# battery_lcl-discharging.net
KiCad netlist of a schematic drawn in Altium Designer
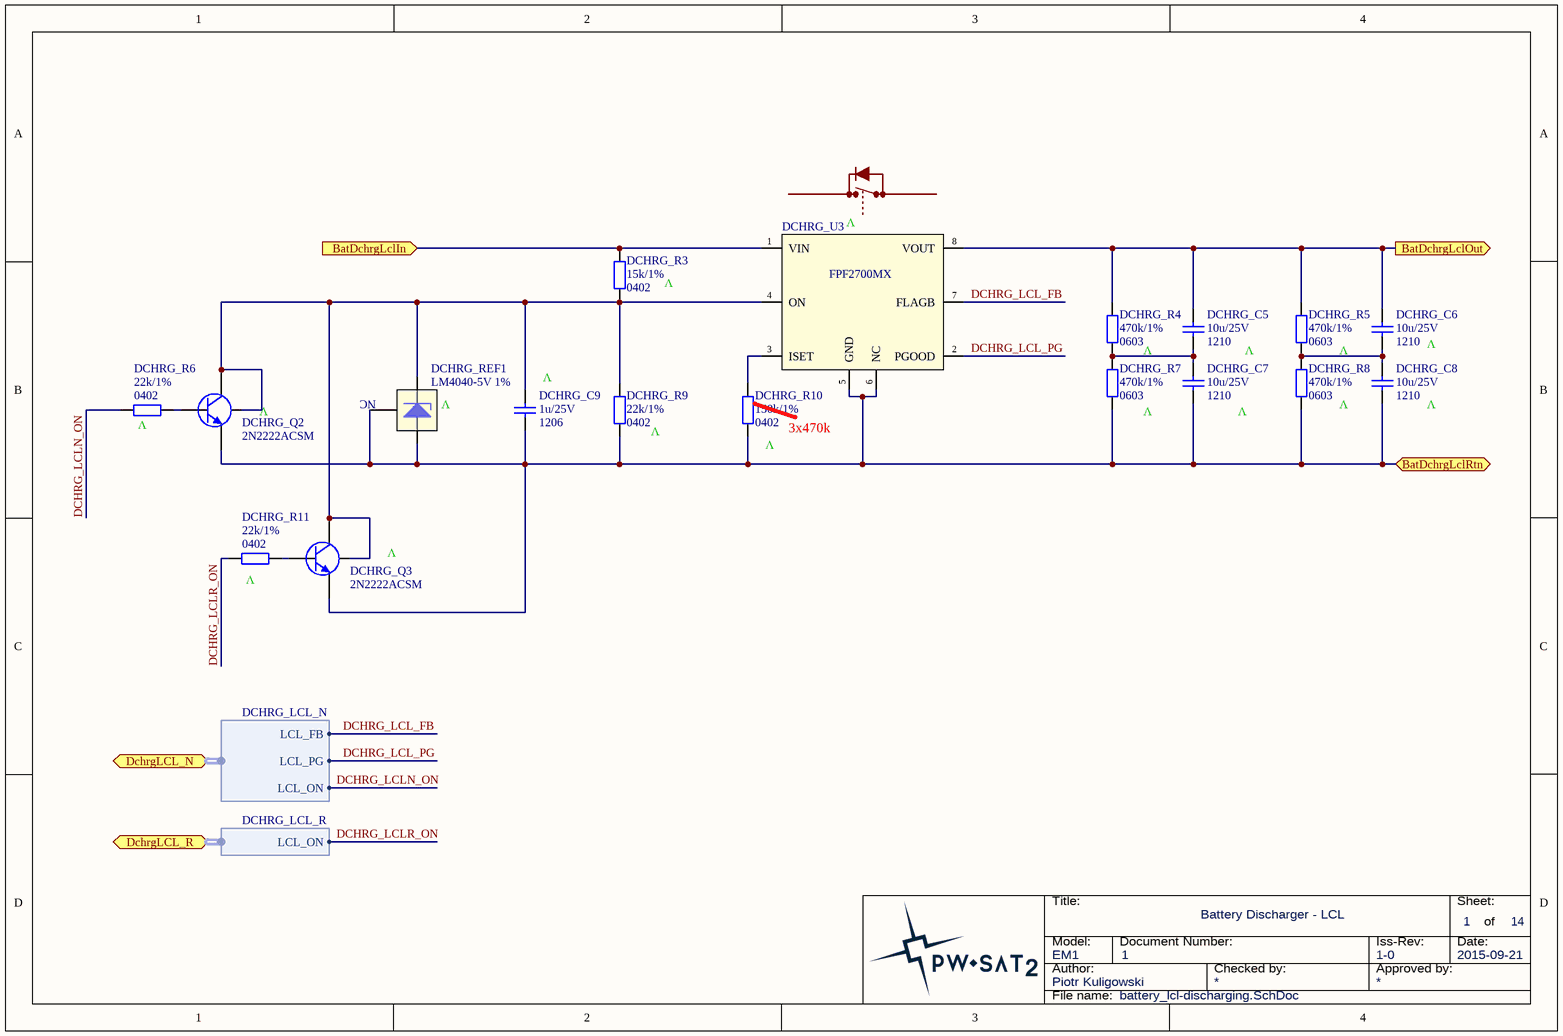
[diagram p0: battery_lcl-discharging.SchDoc]

(export (version "E")
  (design (tool "Eeschema 10.0.6"))
  (components
    (comp (ref "DCHRG_C5")
      (value "10u/25V")
      (footprint "SMD_Capacitor_1210")
      (description "Ceramic Cap Murata Automotive 10u/25V X7R 1210")
      (fields
        (field (name "MANUFACTURER") "Murata")
        (field (name "MANUFACTURERPARTNUMBER") "GCJ32ER71E106KA12L")
        (field (name "PACKAGE") "1210")
      )
      (libsource (lib "capacitors") (part "Cer_GCJ32ER71E106KA12L"))
    )
    (comp (ref "DCHRG_C6")
      (value "10u/25V")
      (footprint "SMD_Capacitor_1210")
      (description "Ceramic Cap Murata Automotive 10u/25V X7R 1210")
      (fields
        (field (name "MANUFACTURER") "Murata")
        (field (name "MANUFACTURERPARTNUMBER") "GCJ32ER71E106KA12L")
        (field (name "PACKAGE") "1210")
      )
      (libsource (lib "capacitors") (part "Cer_GCJ32ER71E106KA12L"))
    )
    (comp (ref "DCHRG_C7")
      (value "10u/25V")
      (footprint "SMD_Capacitor_1210")
      (description "Ceramic Cap Murata Automotive 10u/25V X7R 1210")
      (fields
        (field (name "MANUFACTURER") "Murata")
        (field (name "MANUFACTURERPARTNUMBER") "GCJ32ER71E106KA12L")
        (field (name "PACKAGE") "1210")
      )
      (libsource (lib "capacitors") (part "Cer_GCJ32ER71E106KA12L"))
    )
    (comp (ref "DCHRG_C8")
      (value "10u/25V")
      (footprint "SMD_Capacitor_1210")
      (description "Ceramic Cap Murata Automotive 10u/25V X7R 1210")
      (fields
        (field (name "MANUFACTURER") "Murata")
        (field (name "MANUFACTURERPARTNUMBER") "GCJ32ER71E106KA12L")
        (field (name "PACKAGE") "1210")
      )
      (libsource (lib "capacitors") (part "Cer_GCJ32ER71E106KA12L"))
    )
    (comp (ref "DCHRG_C9")
      (value "1u/25V")
      (footprint "SMD_Capacitor_1206")
      (description "Ceramic Cap Kemet COTS 1u/25V X7R 1206")
      (fields
        (field (name "MANUFACTURERPARTNUMBER") "C1206T105K3RALTU")
        (field (name "MANUFACTURER") "Kemet")
        (field (name "PACKAGE") "1206")
      )
      (libsource (lib "capacitors") (part "Cer_C1206T105K3RALTU"))
    )
    (comp (ref "DCHRG_Q2")
      (value "2N2222ACSM")
      (footprint "LCC1-4_BEC")
      (description "Silicon Planar Epitaxial NPN Transistor.")
      (fields (field (name "MANUFACTURER") "Semelab-TT"))
      (libsource (lib "transistors") (part "2N2222ACSM"))
    )
    (comp (ref "DCHRG_Q3")
      (value "2N2222ACSM")
      (footprint "LCC1-4_BEC")
      (description "Silicon Planar Epitaxial NPN Transistor.")
      (fields (field (name "MANUFACTURER") "Semelab-TT"))
      (libsource (lib "transistors") (part "2N2222ACSM"))
    )
    (comp (ref "DCHRG_R3")
      (value "15k/1%")
      (footprint "SMD_Resistor_0402")
      (description "15k/1% Vishay CRCW 0402 Resistor. 63mW, 100ppm, 50V.")
      (fields
        (field (name "MANUFACTURER") "Vishay")
        (field (name "MANUFACTURERPARTNUMBER") "CRCW040215K0FKxxxx")
        (field (name "PACKAGE") "0402")
      )
      (libsource (lib "resistors") (part "CRCW040215K0FKxxxx"))
    )
    (comp (ref "DCHRG_R4")
      (value "470k/1%")
      (footprint "SMD_Resistor_0603")
      (description "470k/1% Vishay CRCW 0603 Resistor. 100mW, 100ppm, 75V.")
      (fields
        (field (name "MANUFACTURER") "Vishay")
        (field (name "MANUFACTURERPARTNUMBER") "CRCW0603470KFKxxxx")
        (field (name "PACKAGE") "0603")
      )
      (libsource (lib "resistors") (part "CRCW0603470KFKxxxx"))
    )
    (comp (ref "DCHRG_R5")
      (value "470k/1%")
      (footprint "SMD_Resistor_0603")
      (description "470k/1% Vishay CRCW 0603 Resistor. 100mW, 100ppm, 75V.")
      (fields
        (field (name "MANUFACTURER") "Vishay")
        (field (name "MANUFACTURERPARTNUMBER") "CRCW0603470KFKxxxx")
        (field (name "PACKAGE") "0603")
      )
      (libsource (lib "resistors") (part "CRCW0603470KFKxxxx"))
    )
    (comp (ref "DCHRG_R6")
      (value "22k/1%")
      (footprint "SMD_Resistor_0402")
      (description "22k/1% Vishay CRCW 0402 Resistor. 63mW, 100ppm, 50V.")
      (fields
        (field (name "MANUFACTURER") "Vishay")
        (field (name "MANUFACTURERPARTNUMBER") "CRCW040222K0FKxxxx")
        (field (name "PACKAGE") "0402")
      )
      (libsource (lib "resistors") (part "CRCW040222K0FKxxxx"))
    )
    (comp (ref "DCHRG_R7")
      (value "470k/1%")
      (footprint "SMD_Resistor_0603")
      (description "470k/1% Vishay CRCW 0603 Resistor. 100mW, 100ppm, 75V.")
      (fields
        (field (name "MANUFACTURER") "Vishay")
        (field (name "MANUFACTURERPARTNUMBER") "CRCW0603470KFKxxxx")
        (field (name "PACKAGE") "0603")
      )
      (libsource (lib "resistors") (part "CRCW0603470KFKxxxx"))
    )
    (comp (ref "DCHRG_R8")
      (value "470k/1%")
      (footprint "SMD_Resistor_0603")
      (description "470k/1% Vishay CRCW 0603 Resistor. 100mW, 100ppm, 75V.")
      (fields
        (field (name "MANUFACTURER") "Vishay")
        (field (name "MANUFACTURERPARTNUMBER") "CRCW0603470KFKxxxx")
        (field (name "PACKAGE") "0603")
      )
      (libsource (lib "resistors") (part "CRCW0603470KFKxxxx"))
    )
    (comp (ref "DCHRG_R9")
      (value "22k/1%")
      (footprint "SMD_Resistor_0402")
      (description "22k/1% Vishay CRCW 0402 Resistor. 63mW, 100ppm, 50V.")
      (fields
        (field (name "MANUFACTURER") "Vishay")
        (field (name "MANUFACTURERPARTNUMBER") "CRCW040222K0FKxxxx")
        (field (name "PACKAGE") "0402")
      )
      (libsource (lib "") (part "CRCW040222K0FKxxxx_1"))
    )
    (comp (ref "DCHRG_R10")
      (value "150k/1%")
      (footprint "SMD_Resistor_0402")
      (description "150k/1% Vishay CRCW 0402 Resistor. 63mW, 100ppm, 50V.")
      (fields
        (field (name "MANUFACTURER") "Vishay")
        (field (name "MANUFACTURERPARTNUMBER") "CRCW0402150KFKxxxx")
        (field (name "PACKAGE") "0402")
      )
      (libsource (lib "resistors") (part "CRCW0402150KFKxxxx"))
    )
    (comp (ref "DCHRG_R11")
      (value "22k/1%")
      (footprint "SMD_Resistor_0402")
      (description "22k/1% Vishay CRCW 0402 Resistor. 63mW, 100ppm, 50V.")
      (fields
        (field (name "MANUFACTURER") "Vishay")
        (field (name "MANUFACTURERPARTNUMBER") "CRCW040222K0FKxxxx")
        (field (name "PACKAGE") "0402")
      )
      (libsource (lib "resistors") (part "CRCW040222K0FKxxxx"))
    )
    (comp (ref "DCHRG_REF1")
      (value "LM4040-5V 1%")
      (footprint "SOT23-3")
      (description "Shunt V-REF, 5V, 1%, SOT23-3")
      (fields
        (field (name "MANUFACTURER") "Texas Instruments")
        (field (name "MANUFACTURERPARTNUMBER") "LM4040DIM3-5.0")
      )
      (libsource (lib "diodes") (part "LM4040DIM3-5.0"))
    )
    (comp (ref "DCHRG_U3")
      (value "FPF2700MX")
      (footprint "SOIC-8-N")
      (description "Adj over-current protection 0.4-2A, Load Switch")
      (fields (field (name "MANUFACTURER") "Fairchild Semiconductor"))
      (libsource (lib "microcircuits") (part "FPF2700MX"))
    )
  )
  (nets
    (net (code "3") (name "/BatDchrgLclIn") (class "Default")
      (node (ref "DCHRG_R3") (pin "1") (pinfunction "1_1") (pintype "passive"))
      (node (ref "DCHRG_U3") (pin "1") (pinfunction "VIN_1") (pintype "passive"))
    )
    (net (code "4") (name "/BatDchrgLclOut") (class "Default")
      (node (ref "DCHRG_C5") (pin "1") (pinfunction "1_1") (pintype "passive"))
      (node (ref "DCHRG_C6") (pin "1") (pinfunction "1_1") (pintype "passive"))
      (node (ref "DCHRG_R4") (pin "1") (pinfunction "1_1") (pintype "passive"))
      (node (ref "DCHRG_R5") (pin "1") (pinfunction "1_1") (pintype "passive"))
      (node (ref "DCHRG_U3") (pin "8") (pinfunction "VOUT_8") (pintype "passive"))
    )
    (net (code "5") (name "/BatDchrgLclRtn") (class "Default")
      (node (ref "DCHRG_C7") (pin "2") (pinfunction "2_2") (pintype "passive"))
      (node (ref "DCHRG_C8") (pin "2") (pinfunction "2_2") (pintype "passive"))
      (node (ref "DCHRG_C9") (pin "2") (pinfunction "2_2") (pintype "passive"))
      (node (ref "DCHRG_Q2") (pin "E") (pinfunction "E_E") (pintype "passive"))
      (node (ref "DCHRG_Q3") (pin "E") (pinfunction "E_E") (pintype "passive"))
      (node (ref "DCHRG_R10") (pin "2") (pinfunction "2_2") (pintype "passive"))
      (node (ref "DCHRG_R7") (pin "2") (pinfunction "2_2") (pintype "passive"))
      (node (ref "DCHRG_R8") (pin "2") (pinfunction "2_2") (pintype "passive"))
      (node (ref "DCHRG_R9") (pin "2") (pinfunction "2_2") (pintype "passive"))
      (node (ref "DCHRG_REF1") (pin "2") (pinfunction "A_2") (pintype "passive"))
      (node (ref "DCHRG_REF1") (pin "3") (pinfunction "NC_3") (pintype "passive"))
      (node (ref "DCHRG_U3") (pin "5") (pinfunction "GND_5") (pintype "passive"))
      (node (ref "DCHRG_U3") (pin "6") (pinfunction "NC_6") (pintype "passive"))
    )
    (net (code "6") (name "/DCHRG_LCLN_ON") (class "Default")
      (node (ref "DCHRG_R6") (pin "2") (pinfunction "2_2") (pintype "passive"))
    )
    (net (code "7") (name "/DCHRG_LCLR_ON") (class "Default")
      (node (ref "DCHRG_R11") (pin "2") (pinfunction "2_2") (pintype "passive"))
    )
    (net (code "8") (name "/DCHRG_LCL_FB") (class "Default")
      (node (ref "DCHRG_U3") (pin "7") (pinfunction "FLAGB_7") (pintype "passive"))
    )
    (net (code "9") (name "/DCHRG_LCL_PG") (class "Default")
      (node (ref "DCHRG_U3") (pin "2") (pinfunction "PGOOD_2") (pintype "passive"))
    )
    (net (code "12") (name "Net-(DCHRG_C5-Pad2)") (class "Default")
      (node (ref "DCHRG_C5") (pin "2") (pinfunction "2_2") (pintype "passive"))
      (node (ref "DCHRG_C7") (pin "1") (pinfunction "1_1") (pintype "passive"))
      (node (ref "DCHRG_R4") (pin "2") (pinfunction "2_2") (pintype "passive"))
      (node (ref "DCHRG_R7") (pin "1") (pinfunction "1_1") (pintype "passive"))
    )
    (net (code "13") (name "Net-(DCHRG_C6-Pad2)") (class "Default")
      (node (ref "DCHRG_C6") (pin "2") (pinfunction "2_2") (pintype "passive"))
      (node (ref "DCHRG_C8") (pin "1") (pinfunction "1_1") (pintype "passive"))
      (node (ref "DCHRG_R5") (pin "2") (pinfunction "2_2") (pintype "passive"))
      (node (ref "DCHRG_R8") (pin "1") (pinfunction "1_1") (pintype "passive"))
    )
    (net (code "14") (name "Net-(DCHRG_Q2-PadB)") (class "Default")
      (node (ref "DCHRG_Q2") (pin "B") (pinfunction "B_B") (pintype "passive"))
      (node (ref "DCHRG_R6") (pin "1") (pinfunction "1_1") (pintype "passive"))
    )
    (net (code "15") (name "Net-(DCHRG_Q3-PadB)") (class "Default")
      (node (ref "DCHRG_Q3") (pin "B") (pinfunction "B_B") (pintype "passive"))
      (node (ref "DCHRG_R11") (pin "1") (pinfunction "1_1") (pintype "passive"))
    )
    (net (code "16") (name "Net-(DCHRG_REF1-K)") (class "Default")
      (node (ref "DCHRG_C9") (pin "1") (pinfunction "1_1") (pintype "passive"))
      (node (ref "DCHRG_Q2") (pin "C") (pinfunction "C_C") (pintype "passive"))
      (node (ref "DCHRG_Q2") (pin "Shield") (pinfunction "Shield_Shield") (pintype "passive"))
      (node (ref "DCHRG_Q3") (pin "C") (pinfunction "C_C") (pintype "passive"))
      (node (ref "DCHRG_Q3") (pin "Shield") (pinfunction "Shield_Shield") (pintype "passive"))
      (node (ref "DCHRG_R3") (pin "2") (pinfunction "2_2") (pintype "passive"))
      (node (ref "DCHRG_R9") (pin "1") (pinfunction "1_1") (pintype "passive"))
      (node (ref "DCHRG_REF1") (pin "1") (pinfunction "K_1") (pintype "passive"))
      (node (ref "DCHRG_U3") (pin "4") (pinfunction "ON_4") (pintype "passive"))
    )
    (net (code "17") (name "Net-(DCHRG_U3-ISET)") (class "Default")
      (node (ref "DCHRG_R10") (pin "1") (pinfunction "1_1") (pintype "passive"))
      (node (ref "DCHRG_U3") (pin "3") (pinfunction "ISET_3") (pintype "passive"))
    )
  )
)
